# ocf4riser.net
KiCad netlist of a schematic drawn in EAGLE
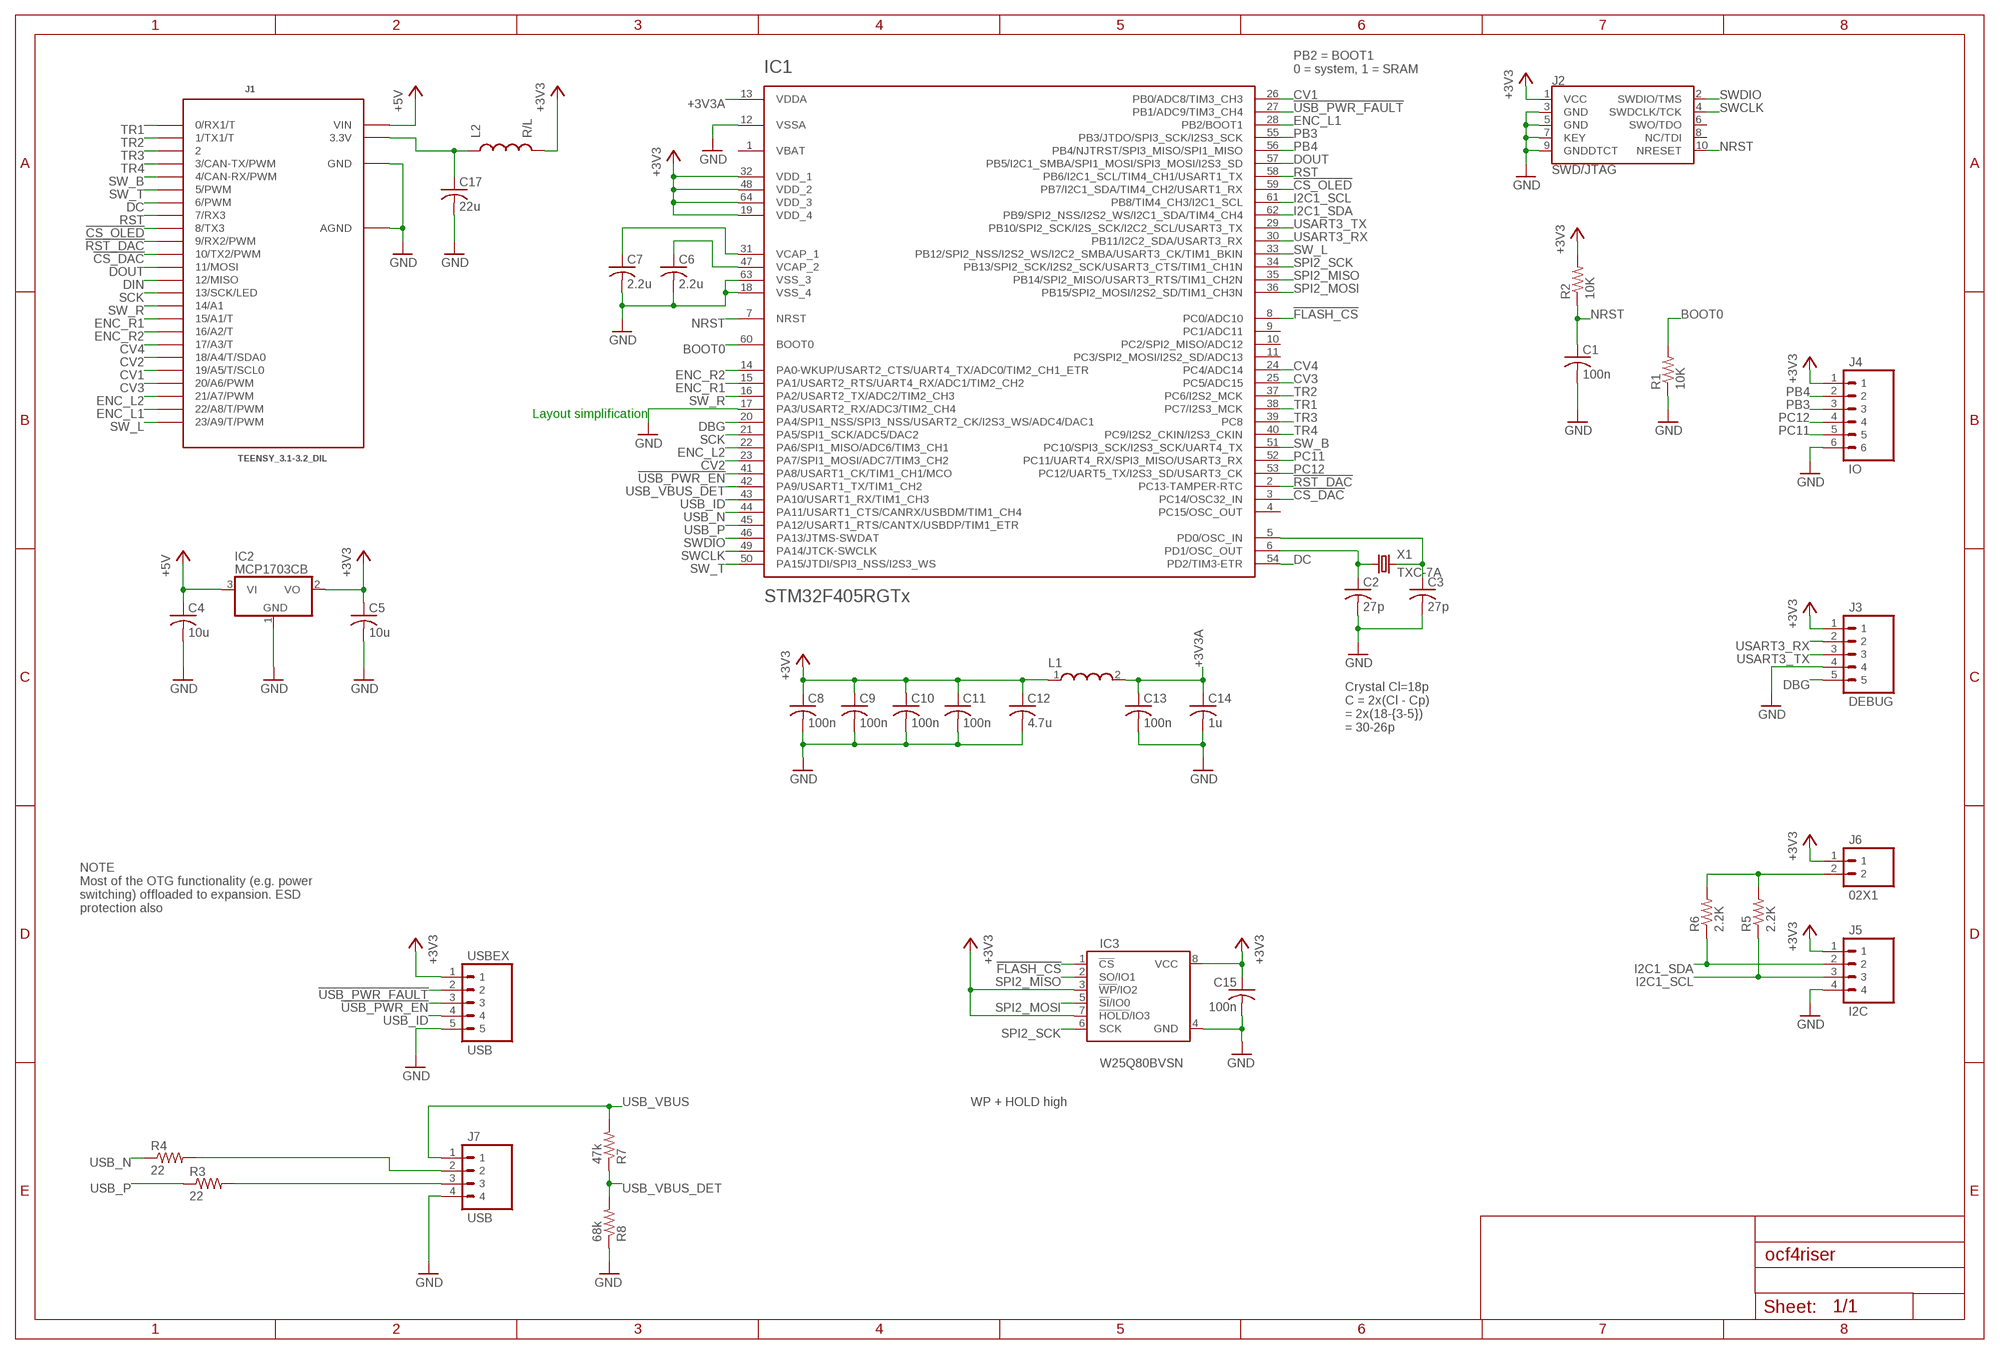
[diagram p0: schematic, sheet 1]

(export (version "E")
  (design (tool "Eeschema 10.0.6"))
  (components
    (comp (ref "C1")
      (value "100n")
      (footprint "eagle-import:C0402")
      (libsource (lib "eagle-import") (part "C-USC0402"))
    )
    (comp (ref "C2")
      (value "27p")
      (footprint "eagle-import:C0402")
      (libsource (lib "eagle-import") (part "C-USC0402"))
    )
    (comp (ref "C3")
      (value "27p")
      (footprint "eagle-import:C0402")
      (libsource (lib "eagle-import") (part "C-USC0402"))
    )
    (comp (ref "C4")
      (value "10u")
      (footprint "eagle-import:C0805")
      (libsource (lib "eagle-import") (part "C-USC0805"))
    )
    (comp (ref "C5")
      (value "10u")
      (footprint "eagle-import:C0805")
      (libsource (lib "eagle-import") (part "C-USC0805"))
    )
    (comp (ref "C6")
      (value "2.2u")
      (footprint "eagle-import:C0603")
      (libsource (lib "eagle-import") (part "C-USC0603"))
    )
    (comp (ref "C7")
      (value "2.2u")
      (footprint "eagle-import:C0603")
      (libsource (lib "eagle-import") (part "C-USC0603"))
    )
    (comp (ref "C8")
      (value "100n")
      (footprint "eagle-import:C0402")
      (libsource (lib "eagle-import") (part "C-USC0402"))
    )
    (comp (ref "C9")
      (value "100n")
      (footprint "eagle-import:C0402")
      (libsource (lib "eagle-import") (part "C-USC0402"))
    )
    (comp (ref "C10")
      (value "100n")
      (footprint "eagle-import:C0402")
      (libsource (lib "eagle-import") (part "C-USC0402"))
    )
    (comp (ref "C11")
      (value "100n")
      (footprint "eagle-import:C0402")
      (libsource (lib "eagle-import") (part "C-USC0402"))
    )
    (comp (ref "C12")
      (value "4.7u")
      (footprint "eagle-import:C0603")
      (libsource (lib "eagle-import") (part "C-USC0603"))
    )
    (comp (ref "C13")
      (value "100n")
      (footprint "eagle-import:C0402")
      (libsource (lib "eagle-import") (part "C-USC0402"))
    )
    (comp (ref "C14")
      (value "1u")
      (footprint "eagle-import:C0603")
      (libsource (lib "eagle-import") (part "C-USC0603"))
    )
    (comp (ref "C15")
      (value "100n")
      (footprint "eagle-import:C0402")
      (libsource (lib "eagle-import") (part "C-USC0402"))
    )
    (comp (ref "C17")
      (value "22u")
      (footprint "eagle-import:C0805")
      (libsource (lib "eagle-import") (part "C-USC0805"))
    )
    (comp (ref "IC1")
      (value "STM32F405RGTx")
      (footprint "eagle-import:TQFP-10X10-64")
      (libsource (lib "eagle-import") (part "STM32F20X"))
    )
    (comp (ref "IC2")
      (value "MCP1703CB")
      (footprint "eagle-import:SOT23")
      (libsource (lib "eagle-import") (part "MCP1703CB"))
    )
    (comp (ref "IC3")
      (value "W25Q80BVSN")
      (footprint "eagle-import:SOIC-8")
      (libsource (lib "eagle-import") (part "SPIFLASHN"))
    )
    (comp (ref "J1")
      (value "TEENSY_3.1-3.2_DIL")
      (footprint "eagle-import:TEENSY_3.0-3.2&LC_DIL")
      (libsource (lib "eagle-import") (part "TEENSY_3.1-3.2_DIL"))
    )
    (comp (ref "J2")
      (value "SWD/JTAG")
      (footprint "eagle-import:2X5-1.27")
      (libsource (lib "eagle-import") (part "CORTEX_DEBUGNAKED"))
    )
    (comp (ref "J3")
      (value "DEBUG")
      (footprint "eagle-import:05X1-THIN")
      (libsource (lib "eagle-import") (part "05X1"))
    )
    (comp (ref "J4")
      (value "IO")
      (footprint "eagle-import:06X1-THIN")
      (libsource (lib "eagle-import") (part "06X1"))
    )
    (comp (ref "J5")
      (value "I2C")
      (footprint "eagle-import:04X1-THIN")
      (libsource (lib "eagle-import") (part "04X1"))
    )
    (comp (ref "J6")
      (value "02X1")
      (footprint "eagle-import:02X1-THIN")
      (libsource (lib "eagle-import") (part "02X1"))
    )
    (comp (ref "J7")
      (value "USB")
      (footprint "eagle-import:04X1-THIN")
      (libsource (lib "eagle-import") (part "04X1"))
    )
    (comp (ref "L1")
      (value "WE-CBF_0603(WB/HS)")
      (footprint "eagle-import:WE-CBF_0603(W=2.2)")
      (libsource (lib "eagle-import") (part "WE-CBF_0603(WB/HS)"))
    )
    (comp (ref "L2")
      (value "R/L")
      (footprint "eagle-import:0805")
      (libsource (lib "eagle-import") (part "INDUCTOR0805"))
    )
    (comp (ref "R1")
      (value "10K")
      (footprint "eagle-import:R0402")
      (libsource (lib "eagle-import") (part "R-US_R0402"))
    )
    (comp (ref "R2")
      (value "10K")
      (footprint "eagle-import:R0402")
      (libsource (lib "eagle-import") (part "R-US_R0402"))
    )
    (comp (ref "R3")
      (value "22")
      (footprint "eagle-import:R0402")
      (libsource (lib "eagle-import") (part "R-US_R0402"))
    )
    (comp (ref "R4")
      (value "22")
      (footprint "eagle-import:R0402")
      (libsource (lib "eagle-import") (part "R-US_R0402"))
    )
    (comp (ref "R5")
      (value "2.2K")
      (footprint "eagle-import:R0603")
      (libsource (lib "eagle-import") (part "R-US_R0603"))
    )
    (comp (ref "R6")
      (value "2.2K")
      (footprint "eagle-import:R0603")
      (libsource (lib "eagle-import") (part "R-US_R0603"))
    )
    (comp (ref "R7")
      (value "47k")
      (footprint "eagle-import:R0402")
      (libsource (lib "eagle-import") (part "R-US_R0402"))
    )
    (comp (ref "R8")
      (value "68k")
      (footprint "eagle-import:R0402")
      (libsource (lib "eagle-import") (part "R-US_R0402"))
    )
    (comp (ref "USBEX")
      (value "USB")
      (footprint "eagle-import:05X1-THIN")
      (libsource (lib "eagle-import") (part "05X1"))
    )
    (comp (ref "X1")
      (value "TXC-7A")
      (footprint "eagle-import:CRYSTAL-TXC-7A")
      (libsource (lib "eagle-import") (part "TXC-7A"))
    )
  )
  (nets
    (net (code "1") (name "+3V3") (class "Default")
      (node (ref "C10") (pin "1") (pinfunction "1_1") (pintype "passive"))
      (node (ref "C11") (pin "1") (pinfunction "1_1") (pintype "passive"))
      (node (ref "C12") (pin "1") (pinfunction "1_1") (pintype "passive"))
      (node (ref "C15") (pin "1") (pinfunction "1_1") (pintype "passive"))
      (node (ref "C5") (pin "1") (pinfunction "1_1") (pintype "passive"))
      (node (ref "C8") (pin "1") (pinfunction "1_1") (pintype "passive"))
      (node (ref "C9") (pin "1") (pinfunction "1_1") (pintype "passive"))
      (node (ref "IC1") (pin "19") (pinfunction "VDD_4_19") (pintype "power_in"))
      (node (ref "IC1") (pin "32") (pinfunction "VDD_1_32") (pintype "power_in"))
      (node (ref "IC1") (pin "48") (pinfunction "VDD_2_48") (pintype "power_in"))
      (node (ref "IC1") (pin "64") (pinfunction "VDD_3_64") (pintype "power_in"))
      (node (ref "IC2") (pin "2") (pinfunction "VO_2") (pintype "passive"))
      (node (ref "IC3") (pin "3") (pinfunction "~{WP}/IO2_3") (pintype "bidirectional"))
      (node (ref "IC3") (pin "7") (pinfunction "~{HOLD}/IO3_7") (pintype "bidirectional"))
      (node (ref "IC3") (pin "8") (pinfunction "VCC_8") (pintype "power_in"))
      (node (ref "J2") (pin "1") (pinfunction "VCC_1") (pintype "bidirectional"))
      (node (ref "J3") (pin "1") (pinfunction "1_1") (pintype "passive"))
      (node (ref "J4") (pin "1") (pinfunction "1_1") (pintype "passive"))
      (node (ref "J5") (pin "1") (pinfunction "1_1") (pintype "passive"))
      (node (ref "J6") (pin "1") (pinfunction "1_1") (pintype "passive"))
      (node (ref "L1") (pin "1") (pinfunction "1_1") (pintype "passive"))
      (node (ref "L2") (pin "2") (pinfunction "2_2") (pintype "passive"))
      (node (ref "R2") (pin "2") (pinfunction "2_2") (pintype "passive"))
      (node (ref "USBEX") (pin "1") (pinfunction "1_1") (pintype "passive"))
    )
    (net (code "2") (name "+5V") (class "Default")
      (node (ref "C4") (pin "1") (pinfunction "1_1") (pintype "passive"))
      (node (ref "IC2") (pin "3") (pinfunction "VI_3") (pintype "input"))
      (node (ref "J1") (pin "VIN") (pinfunction "VIN_VIN") (pintype "power_in"))
    )
    (net (code "3") (name "/+3V3A") (class "Default")
      (node (ref "C13") (pin "1") (pinfunction "1_1") (pintype "passive"))
      (node (ref "C14") (pin "1") (pinfunction "1_1") (pintype "passive"))
      (node (ref "IC1") (pin "13") (pinfunction "VDDA_13") (pintype "power_in"))
      (node (ref "L1") (pin "2") (pinfunction "2_2") (pintype "passive"))
    )
    (net (code "4") (name "/BOOT0") (class "Default")
      (node (ref "IC1") (pin "60") (pinfunction "BOOT0_60") (pintype "bidirectional"))
      (node (ref "R1") (pin "2") (pinfunction "2_2") (pintype "passive"))
    )
    (net (code "5") (name "/CV1") (class "Default")
      (node (ref "IC1") (pin "26") (pinfunction "PB0/ADC8/TIM3_CH3_26") (pintype "bidirectional"))
      (node (ref "J1") (pin "19/A5") (pinfunction "19/A5/T/SCL0_19/A5") (pintype "bidirectional"))
    )
    (net (code "6") (name "/CV2") (class "Default")
      (node (ref "IC1") (pin "23") (pinfunction "PA7/SPI1_MOSI/ADC7/TIM3_CH2_23") (pintype "bidirectional"))
      (node (ref "J1") (pin "18/A4") (pinfunction "18/A4/T/SDA0_18/A4") (pintype "bidirectional"))
    )
    (net (code "7") (name "/CV3") (class "Default")
      (node (ref "IC1") (pin "25") (pinfunction "PC5/ADC15_25") (pintype "bidirectional"))
      (node (ref "J1") (pin "20/A6") (pinfunction "20/A6/PWM_20/A6") (pintype "bidirectional"))
    )
    (net (code "8") (name "/CV4") (class "Default")
      (node (ref "IC1") (pin "24") (pinfunction "PC4/ADC14_24") (pintype "bidirectional"))
      (node (ref "J1") (pin "17/A3") (pinfunction "17/A3/T_17/A3") (pintype "bidirectional"))
    )
    (net (code "9") (name "/DBG") (class "Default")
      (node (ref "IC1") (pin "20") (pinfunction "PA4/SPI1_NSS/SPI3_NSS/USART2_CK/I2S3_WS/ADC4/DAC1_20") (pintype "bidirectional"))
      (node (ref "J3") (pin "5") (pinfunction "5_5") (pintype "passive"))
    )
    (net (code "10") (name "/DC") (class "Default")
      (node (ref "IC1") (pin "54") (pinfunction "PD2/TIM3-ETR_54") (pintype "bidirectional"))
      (node (ref "J1") (pin "6") (pinfunction "6/PWM_6") (pintype "bidirectional"))
    )
    (net (code "11") (name "/DIN") (class "Default")
      (node (ref "J1") (pin "12") (pinfunction "12/MISO_12") (pintype "bidirectional"))
    )
    (net (code "12") (name "/DOUT") (class "Default")
      (node (ref "IC1") (pin "57") (pinfunction "PB5/I2C1_SMBA/SPI1_MOSI/SPI3_MOSI/I2S3_SD_57") (pintype "bidirectional"))
      (node (ref "J1") (pin "11") (pinfunction "11/MOSI_11") (pintype "bidirectional"))
    )
    (net (code "13") (name "/ENC_L1") (class "Default")
      (node (ref "IC1") (pin "28") (pinfunction "PB2/BOOT1_28") (pintype "bidirectional"))
      (node (ref "J1") (pin "22/A8") (pinfunction "22/A8/T/PWM_22/A8") (pintype "bidirectional"))
    )
    (net (code "14") (name "/ENC_L2") (class "Default")
      (node (ref "IC1") (pin "22") (pinfunction "PA6/SPI1_MISO/ADC6/TIM3_CH1_22") (pintype "bidirectional"))
      (node (ref "J1") (pin "21/A7") (pinfunction "21/A7/PWM_21/A7") (pintype "bidirectional"))
    )
    (net (code "15") (name "/ENC_R1") (class "Default")
      (node (ref "IC1") (pin "15") (pinfunction "PA1/USART2_RTS/UART4_RX/ADC1/TIM2_CH2_15") (pintype "bidirectional"))
      (node (ref "J1") (pin "15/A1") (pinfunction "15/A1/T_15/A1") (pintype "bidirectional"))
    )
    (net (code "16") (name "/ENC_R2") (class "Default")
      (node (ref "IC1") (pin "14") (pinfunction "PA0-WKUP/USART2_CTS/UART4_TX/ADC0/TIM2_CH1_ETR_14") (pintype "bidirectional"))
      (node (ref "J1") (pin "16/A2") (pinfunction "16/A2/T_16/A2") (pintype "bidirectional"))
    )
    (net (code "17") (name "/I2C1_SCL") (class "Default")
      (node (ref "IC1") (pin "61") (pinfunction "PB8/TIM4_CH3/I2C1_SCL_61") (pintype "bidirectional"))
      (node (ref "J5") (pin "3") (pinfunction "3_3") (pintype "passive"))
      (node (ref "R5") (pin "1") (pinfunction "1_1") (pintype "passive"))
    )
    (net (code "18") (name "/I2C1_SDA") (class "Default")
      (node (ref "IC1") (pin "62") (pinfunction "PB9/SPI2_NSS/I2S2_WS/I2C1_SDA/TIM4_CH4_62") (pintype "bidirectional"))
      (node (ref "J5") (pin "2") (pinfunction "2_2") (pintype "passive"))
      (node (ref "R6") (pin "1") (pinfunction "1_1") (pintype "passive"))
    )
    (net (code "19") (name "/NRST") (class "Default")
      (node (ref "C1") (pin "1") (pinfunction "1_1") (pintype "passive"))
      (node (ref "IC1") (pin "7") (pinfunction "NRST_7") (pintype "bidirectional"))
      (node (ref "J2") (pin "10") (pinfunction "NRESET_10") (pintype "bidirectional"))
      (node (ref "R2") (pin "1") (pinfunction "1_1") (pintype "passive"))
    )
    (net (code "20") (name "/PB3") (class "Default")
      (node (ref "IC1") (pin "55") (pinfunction "PB3/JTDO/SPI3_SCK/I2S3_SCK_55") (pintype "bidirectional"))
      (node (ref "J4") (pin "3") (pinfunction "3_3") (pintype "passive"))
    )
    (net (code "21") (name "/PB4") (class "Default")
      (node (ref "IC1") (pin "56") (pinfunction "PB4/NJTRST/SPI3_MISO/SPI1_MISO_56") (pintype "bidirectional"))
      (node (ref "J4") (pin "2") (pinfunction "2_2") (pintype "passive"))
    )
    (net (code "22") (name "/PC11") (class "Default")
      (node (ref "IC1") (pin "52") (pinfunction "PC11/UART4_RX/SPI3_MISO/USART3_RX_52") (pintype "bidirectional"))
      (node (ref "J4") (pin "5") (pinfunction "5_5") (pintype "passive"))
    )
    (net (code "23") (name "/PC12") (class "Default")
      (node (ref "IC1") (pin "53") (pinfunction "PC12/UART5_TX/I2S3_SD/USART3_CK_53") (pintype "bidirectional"))
      (node (ref "J4") (pin "4") (pinfunction "4_4") (pintype "passive"))
    )
    (net (code "24") (name "/RST") (class "Default")
      (node (ref "IC1") (pin "58") (pinfunction "PB6/I2C1_SCL/TIM4_CH1/USART1_TX_58") (pintype "bidirectional"))
      (node (ref "J1") (pin "7") (pinfunction "7/RX3_7") (pintype "bidirectional"))
    )
    (net (code "25") (name "/SCK") (class "Default")
      (node (ref "IC1") (pin "21") (pinfunction "PA5/SPI1_SCK/ADC5/DAC2_21") (pintype "bidirectional"))
      (node (ref "J1") (pin "13") (pinfunction "13/SCK/LED_13") (pintype "bidirectional"))
    )
    (net (code "26") (name "/SPI2_MISO") (class "Default")
      (node (ref "IC1") (pin "35") (pinfunction "PB14/SPI2_MISO/USART3_RTS/TIM1_CH2N_35") (pintype "bidirectional"))
      (node (ref "IC3") (pin "2") (pinfunction "SO/IO1_2") (pintype "bidirectional"))
    )
    (net (code "27") (name "/SPI2_MOSI") (class "Default")
      (node (ref "IC1") (pin "36") (pinfunction "PB15/SPI2_MOSI/I2S2_SD/TIM1_CH3N_36") (pintype "bidirectional"))
      (node (ref "IC3") (pin "5") (pinfunction "~{SI}/IO0_5") (pintype "bidirectional"))
    )
    (net (code "28") (name "/SPI2_SCK") (class "Default")
      (node (ref "IC1") (pin "34") (pinfunction "PB13/SPI2_SCK/I2S2_SCK/USART3_CTS/TIM1_CH1N_34") (pintype "bidirectional"))
      (node (ref "IC3") (pin "6") (pinfunction "SCK_6") (pintype "bidirectional"))
    )
    (net (code "29") (name "/SWCLK") (class "Default")
      (node (ref "IC1") (pin "49") (pinfunction "PA14/JTCK-SWCLK_49") (pintype "bidirectional"))
      (node (ref "J2") (pin "4") (pinfunction "SWDCLK/TCK_4") (pintype "bidirectional"))
    )
    (net (code "30") (name "/SWDIO") (class "Default")
      (node (ref "IC1") (pin "46") (pinfunction "PA13/JTMS-SWDAT_46") (pintype "bidirectional"))
      (node (ref "J2") (pin "2") (pinfunction "SWDIO/TMS_2") (pintype "bidirectional"))
    )
    (net (code "31") (name "/SW_B") (class "Default")
      (node (ref "IC1") (pin "51") (pinfunction "PC10/SPI3_SCK/I2S3_SCK/UART4_TX_51") (pintype "bidirectional"))
      (node (ref "J1") (pin "4") (pinfunction "4/CAN-RX/PWM_4") (pintype "bidirectional"))
    )
    (net (code "32") (name "/SW_L") (class "Default")
      (node (ref "IC1") (pin "33") (pinfunction "PB12/SPI2_NSS/I2S2_WS/I2C2_SMBA/USART3_CK/TIM1_BKIN_33") (pintype "bidirectional"))
      (node (ref "J1") (pin "23/A9") (pinfunction "23/A9/T/PWM_23/A9") (pintype "bidirectional"))
    )
    (net (code "33") (name "/SW_R") (class "Default")
      (node (ref "IC1") (pin "16") (pinfunction "PA2/USART2_TX/ADC2/TIM2_CH3_16") (pintype "bidirectional"))
      (node (ref "J1") (pin "14/A0") (pinfunction "14/A1_14/A0") (pintype "bidirectional"))
    )
    (net (code "34") (name "/SW_T") (class "Default")
      (node (ref "IC1") (pin "50") (pinfunction "PA15/JTDI/SPI3_NSS/I2S3_WS_50") (pintype "bidirectional"))
      (node (ref "J1") (pin "5") (pinfunction "5/PWM_5") (pintype "bidirectional"))
    )
    (net (code "35") (name "/TR1") (class "Default")
      (node (ref "IC1") (pin "38") (pinfunction "PC7/I2S3_MCK_38") (pintype "bidirectional"))
      (node (ref "J1") (pin "0") (pinfunction "0/RX1/T_0") (pintype "bidirectional"))
    )
    (net (code "36") (name "/TR2") (class "Default")
      (node (ref "IC1") (pin "37") (pinfunction "PC6/I2S2_MCK_37") (pintype "bidirectional"))
      (node (ref "J1") (pin "1") (pinfunction "1/TX1/T_1") (pintype "bidirectional"))
    )
    (net (code "37") (name "/TR3") (class "Default")
      (node (ref "IC1") (pin "39") (pinfunction "PC8_39") (pintype "bidirectional"))
      (node (ref "J1") (pin "2") (pinfunction "2_2") (pintype "bidirectional"))
    )
    (net (code "38") (name "/TR4") (class "Default")
      (node (ref "IC1") (pin "40") (pinfunction "PC9/I2S2_CKIN/I2S3_CKIN_40") (pintype "bidirectional"))
      (node (ref "J1") (pin "3") (pinfunction "3/CAN-TX/PWM_3") (pintype "bidirectional"))
    )
    (net (code "39") (name "/USART3_RX") (class "Default")
      (node (ref "IC1") (pin "30") (pinfunction "PB11/I2C2_SDA/USART3_RX_30") (pintype "bidirectional"))
      (node (ref "J3") (pin "2") (pinfunction "2_2") (pintype "passive"))
    )
    (net (code "40") (name "/USART3_TX") (class "Default")
      (node (ref "IC1") (pin "29") (pinfunction "PB10/SPI2_SCK/I2S_SCK/I2C2_SCL/USART3_TX_29") (pintype "bidirectional"))
      (node (ref "J3") (pin "3") (pinfunction "3_3") (pintype "passive"))
    )
    (net (code "41") (name "/USB_ID") (class "Default")
      (node (ref "IC1") (pin "43") (pinfunction "PA10/USART1_RX/TIM1_CH3_43") (pintype "bidirectional"))
      (node (ref "USBEX") (pin "4") (pinfunction "4_4") (pintype "passive"))
    )
    (net (code "42") (name "/USB_N") (class "Default")
      (node (ref "IC1") (pin "44") (pinfunction "PA11/USART1_CTS/CANRX/USBDM/TIM1_CH4_44") (pintype "bidirectional"))
      (node (ref "R4") (pin "1") (pinfunction "1_1") (pintype "passive"))
    )
    (net (code "43") (name "/USB_P") (class "Default")
      (node (ref "IC1") (pin "45") (pinfunction "PA12/USART1_RTS/CANTX/USBDP/TIM1_ETR_45") (pintype "bidirectional"))
      (node (ref "R3") (pin "1") (pinfunction "1_1") (pintype "passive"))
    )
    (net (code "44") (name "/USB_VBUS") (class "Default")
      (node (ref "J7") (pin "1") (pinfunction "1_1") (pintype "passive"))
      (node (ref "R7") (pin "2") (pinfunction "2_2") (pintype "passive"))
    )
    (net (code "45") (name "/USB_VBUS_DET") (class "Default")
      (node (ref "IC1") (pin "42") (pinfunction "PA9/USART1_TX/TIM1_CH2_42") (pintype "bidirectional"))
      (node (ref "R7") (pin "1") (pinfunction "1_1") (pintype "passive"))
      (node (ref "R8") (pin "2") (pinfunction "2_2") (pintype "passive"))
    )
    (net (code "46") (name "/VBAT") (class "Default")
      (node (ref "IC1") (pin "1") (pinfunction "VBAT_1") (pintype "power_in"))
    )
    (net (code "47") (name "/~{CS_DAC}") (class "Default")
      (node (ref "IC1") (pin "3") (pinfunction "PC14/OSC32_IN_3") (pintype "bidirectional"))
      (node (ref "J1") (pin "10") (pinfunction "10/TX2/PWM_10") (pintype "bidirectional"))
    )
    (net (code "48") (name "/~{CS_OLED}") (class "Default")
      (node (ref "IC1") (pin "59") (pinfunction "PB7/I2C1_SDA/TIM4_CH2/USART1_RX_59") (pintype "bidirectional"))
      (node (ref "J1") (pin "8") (pinfunction "8/TX3_8") (pintype "bidirectional"))
    )
    (net (code "49") (name "/~{FLASH_CS}") (class "Default")
      (node (ref "IC1") (pin "8") (pinfunction "PC0/ADC10_8") (pintype "bidirectional"))
      (node (ref "IC3") (pin "1") (pinfunction "~{CS}_1") (pintype "bidirectional"))
    )
    (net (code "50") (name "/~{RST_DAC}") (class "Default")
      (node (ref "IC1") (pin "2") (pinfunction "PC13-TAMPER-RTC_2") (pintype "bidirectional"))
      (node (ref "J1") (pin "9") (pinfunction "9/RX2/PWM_9") (pintype "bidirectional"))
    )
    (net (code "51") (name "/~{USB_PWR_EN}") (class "Default")
      (node (ref "IC1") (pin "41") (pinfunction "PA8/USART1_CK/TIM1_CH1/MCO_41") (pintype "bidirectional"))
      (node (ref "USBEX") (pin "3") (pinfunction "3_3") (pintype "passive"))
    )
    (net (code "52") (name "/~{USB_PWR_FAULT}") (class "Default")
      (node (ref "IC1") (pin "27") (pinfunction "PB1/ADC9/TIM3_CH4_27") (pintype "bidirectional"))
      (node (ref "USBEX") (pin "2") (pinfunction "2_2") (pintype "passive"))
    )
    (net (code "53") (name "GND") (class "Default")
      (node (ref "C1") (pin "2") (pinfunction "2_2") (pintype "passive"))
      (node (ref "C10") (pin "2") (pinfunction "2_2") (pintype "passive"))
      (node (ref "C11") (pin "2") (pinfunction "2_2") (pintype "passive"))
      (node (ref "C12") (pin "2") (pinfunction "2_2") (pintype "passive"))
      (node (ref "C13") (pin "2") (pinfunction "2_2") (pintype "passive"))
      (node (ref "C14") (pin "2") (pinfunction "2_2") (pintype "passive"))
      (node (ref "C15") (pin "2") (pinfunction "2_2") (pintype "passive"))
      (node (ref "C17") (pin "2") (pinfunction "2_2") (pintype "passive"))
      (node (ref "C2") (pin "2") (pinfunction "2_2") (pintype "passive"))
      (node (ref "C3") (pin "2") (pinfunction "2_2") (pintype "passive"))
      (node (ref "C4") (pin "2") (pinfunction "2_2") (pintype "passive"))
      (node (ref "C5") (pin "2") (pinfunction "2_2") (pintype "passive"))
      (node (ref "C6") (pin "2") (pinfunction "2_2") (pintype "passive"))
      (node (ref "C7") (pin "2") (pinfunction "2_2") (pintype "passive"))
      (node (ref "C8") (pin "2") (pinfunction "2_2") (pintype "passive"))
      (node (ref "C9") (pin "2") (pinfunction "2_2") (pintype "passive"))
      (node (ref "IC1") (pin "12") (pinfunction "VSSA_12") (pintype "power_in"))
      (node (ref "IC1") (pin "17") (pinfunction "PA3/USART2_RX/ADC3/TIM2_CH4_17") (pintype "bidirectional"))
      (node (ref "IC1") (pin "18") (pinfunction "VSS_4_18") (pintype "power_in"))
      (node (ref "IC1") (pin "63") (pinfunction "VSS_3_63") (pintype "power_in"))
      (node (ref "IC2") (pin "1") (pinfunction "GND_1") (pintype "passive"))
      (node (ref "IC3") (pin "4") (pinfunction "GND_4") (pintype "power_in"))
      (node (ref "J1") (pin "AGND") (pinfunction "AGND_AGND") (pintype "power_in"))
      (node (ref "J1") (pin "GND") (pinfunction "GND_GND") (pintype "power_in"))
      (node (ref "J2") (pin "3") (pinfunction "GND_3") (pintype "bidirectional"))
      (node (ref "J2") (pin "5") (pinfunction "GND_5") (pintype "bidirectional"))
      (node (ref "J2") (pin "7") (pinfunction "KEY_7") (pintype "bidirectional"))
      (node (ref "J2") (pin "9") (pinfunction "GNDDTCT_9") (pintype "bidirectional"))
      (node (ref "J3") (pin "4") (pinfunction "4_4") (pintype "passive"))
      (node (ref "J4") (pin "6") (pinfunction "6_6") (pintype "passive"))
      (node (ref "J5") (pin "4") (pinfunction "4_4") (pintype "passive"))
      (node (ref "J7") (pin "4") (pinfunction "4_4") (pintype "passive"))
      (node (ref "R1") (pin "1") (pinfunction "1_1") (pintype "passive"))
      (node (ref "R8") (pin "1") (pinfunction "1_1") (pintype "passive"))
      (node (ref "USBEX") (pin "5") (pinfunction "5_5") (pintype "passive"))
    )
    (net (code "54") (name "Net-(C17-Pad1)") (class "Default")
      (node (ref "C17") (pin "1") (pinfunction "1_1") (pintype "passive"))
      (node (ref "J1") (pin "3.3V") (pinfunction "3.3V_3.3V") (pintype "power_in"))
      (node (ref "L2") (pin "1") (pinfunction "1_1") (pintype "passive"))
    )
    (net (code "55") (name "Net-(IC1-PD0{slash}OSC_IN)") (class "Default")
      (node (ref "C3") (pin "1") (pinfunction "1_1") (pintype "passive"))
      (node (ref "IC1") (pin "5") (pinfunction "PD0/OSC_IN_5") (pintype "bidirectional"))
      (node (ref "X1") (pin "P$2") (pinfunction "2_P$2") (pintype "passive"))
    )
    (net (code "56") (name "Net-(IC1-PD1{slash}OSC_OUT)") (class "Default")
      (node (ref "C2") (pin "1") (pinfunction "1_1") (pintype "passive"))
      (node (ref "IC1") (pin "6") (pinfunction "PD1/OSC_OUT_6") (pintype "bidirectional"))
      (node (ref "X1") (pin "P$1") (pinfunction "1_P$1") (pintype "passive"))
    )
    (net (code "57") (name "Net-(IC1-VCAP_1)") (class "Default")
      (node (ref "C7") (pin "1") (pinfunction "1_1") (pintype "passive"))
      (node (ref "IC1") (pin "31") (pinfunction "VCAP_1_31") (pintype "power_in"))
    )
    (net (code "58") (name "Net-(IC1-VCAP_2)") (class "Default")
      (node (ref "C6") (pin "1") (pinfunction "1_1") (pintype "passive"))
      (node (ref "IC1") (pin "47") (pinfunction "VCAP_2_47") (pintype "power_in"))
    )
    (net (code "59") (name "Net-(J6-Pad2)") (class "Default")
      (node (ref "J6") (pin "2") (pinfunction "2_2") (pintype "passive"))
      (node (ref "R5") (pin "2") (pinfunction "2_2") (pintype "passive"))
      (node (ref "R6") (pin "2") (pinfunction "2_2") (pintype "passive"))
    )
    (net (code "60") (name "Net-(J7-Pad2)") (class "Default")
      (node (ref "J7") (pin "2") (pinfunction "2_2") (pintype "passive"))
      (node (ref "R4") (pin "2") (pinfunction "2_2") (pintype "passive"))
    )
    (net (code "61") (name "Net-(J7-Pad3)") (class "Default")
      (node (ref "J7") (pin "3") (pinfunction "3_3") (pintype "passive"))
      (node (ref "R3") (pin "2") (pinfunction "2_2") (pintype "passive"))
    )
    (net (code "62") (name "unconnected-(IC1-PC1{slash}ADC11-Pad9)") (class "Default")
      (node (ref "IC1") (pin "9") (pinfunction "PC1/ADC11_9") (pintype "bidirectional"))
    )
    (net (code "63") (name "unconnected-(IC1-PC2{slash}SPI2_MISO{slash}ADC12-Pad10)") (class "Default")
      (node (ref "IC1") (pin "10") (pinfunction "PC2/SPI2_MISO/ADC12_10") (pintype "bidirectional"))
    )
    (net (code "64") (name "unconnected-(IC1-PC3{slash}SPI2_MOSI{slash}I2S2_SD{slash}ADC13-Pad11)") (class "Default")
      (node (ref "IC1") (pin "11") (pinfunction "PC3/SPI2_MOSI/I2S2_SD/ADC13_11") (pintype "bidirectional"))
    )
    (net (code "65") (name "unconnected-(IC1-PC15{slash}OSC_OUT-Pad4)") (class "Default")
      (node (ref "IC1") (pin "4") (pinfunction "PC15/OSC_OUT_4") (pintype "bidirectional"))
    )
    (net (code "66") (name "unconnected-(J2-NC{slash}TDI-Pad8)") (class "Default")
      (node (ref "J2") (pin "8") (pinfunction "NC/TDI_8") (pintype "bidirectional"))
    )
    (net (code "67") (name "unconnected-(J2-SWO{slash}TDO-Pad6)") (class "Default")
      (node (ref "J2") (pin "6") (pinfunction "SWO/TDO_6") (pintype "bidirectional"))
    )
  )
)
